# ArduSensor-Arcade.net
KiCad netlist of a schematic drawn in EAGLE
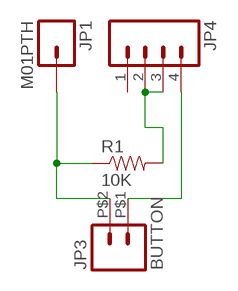
[diagram p0: schematic, sheet 1]

(export (version "E")
  (design (tool "Eeschema 10.0.6"))
  (components
    (comp (ref "JP1")
      (value "M01PTH")
      (footprint "eagle-import:1X01")
      (libsource (lib "eagle-import") (part "M01PTH"))
    )
    (comp (ref "JP3")
      (value "BUTTON")
      (footprint "eagle-import:1X02_BIG")
      (libsource (lib "eagle-import") (part "M02PTH2"))
    )
    (comp (ref "JP4")
      (value "M04PTH")
      (footprint "eagle-import:1X04")
      (libsource (lib "eagle-import") (part "M04PTH"))
    )
    (comp (ref "R1")
      (value "10K")
      (footprint "eagle-import:AXIAL-0.3")
      (libsource (lib "eagle-import") (part "RESISTORAXIAL-0.3"))
    )
  )
  (nets
    (net (code "1") (name "Net-(JP3-1)") (class "Default")
      (node (ref "JP3") (pin "P$1") (pinfunction "1_P$1") (pintype "passive"))
      (node (ref "JP4") (pin "4") (pinfunction "4_4") (pintype "passive"))
    )
    (net (code "2") (name "Net-(JP3-2)") (class "Default")
      (node (ref "JP1") (pin "1") (pinfunction "1_1") (pintype "passive"))
      (node (ref "JP3") (pin "P$2") (pinfunction "2_P$2") (pintype "passive"))
      (node (ref "R1") (pin "P$1") (pinfunction "1_P$1") (pintype "passive"))
    )
    (net (code "3") (name "Net-(R1-2)") (class "Default")
      (node (ref "JP4") (pin "2") (pinfunction "2_2") (pintype "passive"))
      (node (ref "JP4") (pin "3") (pinfunction "3_3") (pintype "passive"))
      (node (ref "R1") (pin "P$2") (pinfunction "2_P$2") (pintype "passive"))
    )
    (net (code "4") (name "unconnected-(JP4-Pad1)") (class "Default")
      (node (ref "JP4") (pin "1") (pinfunction "1_1") (pintype "passive"))
    )
  )
)
